# heehaw10.net
KiCad netlist of a schematic drawn in EAGLE
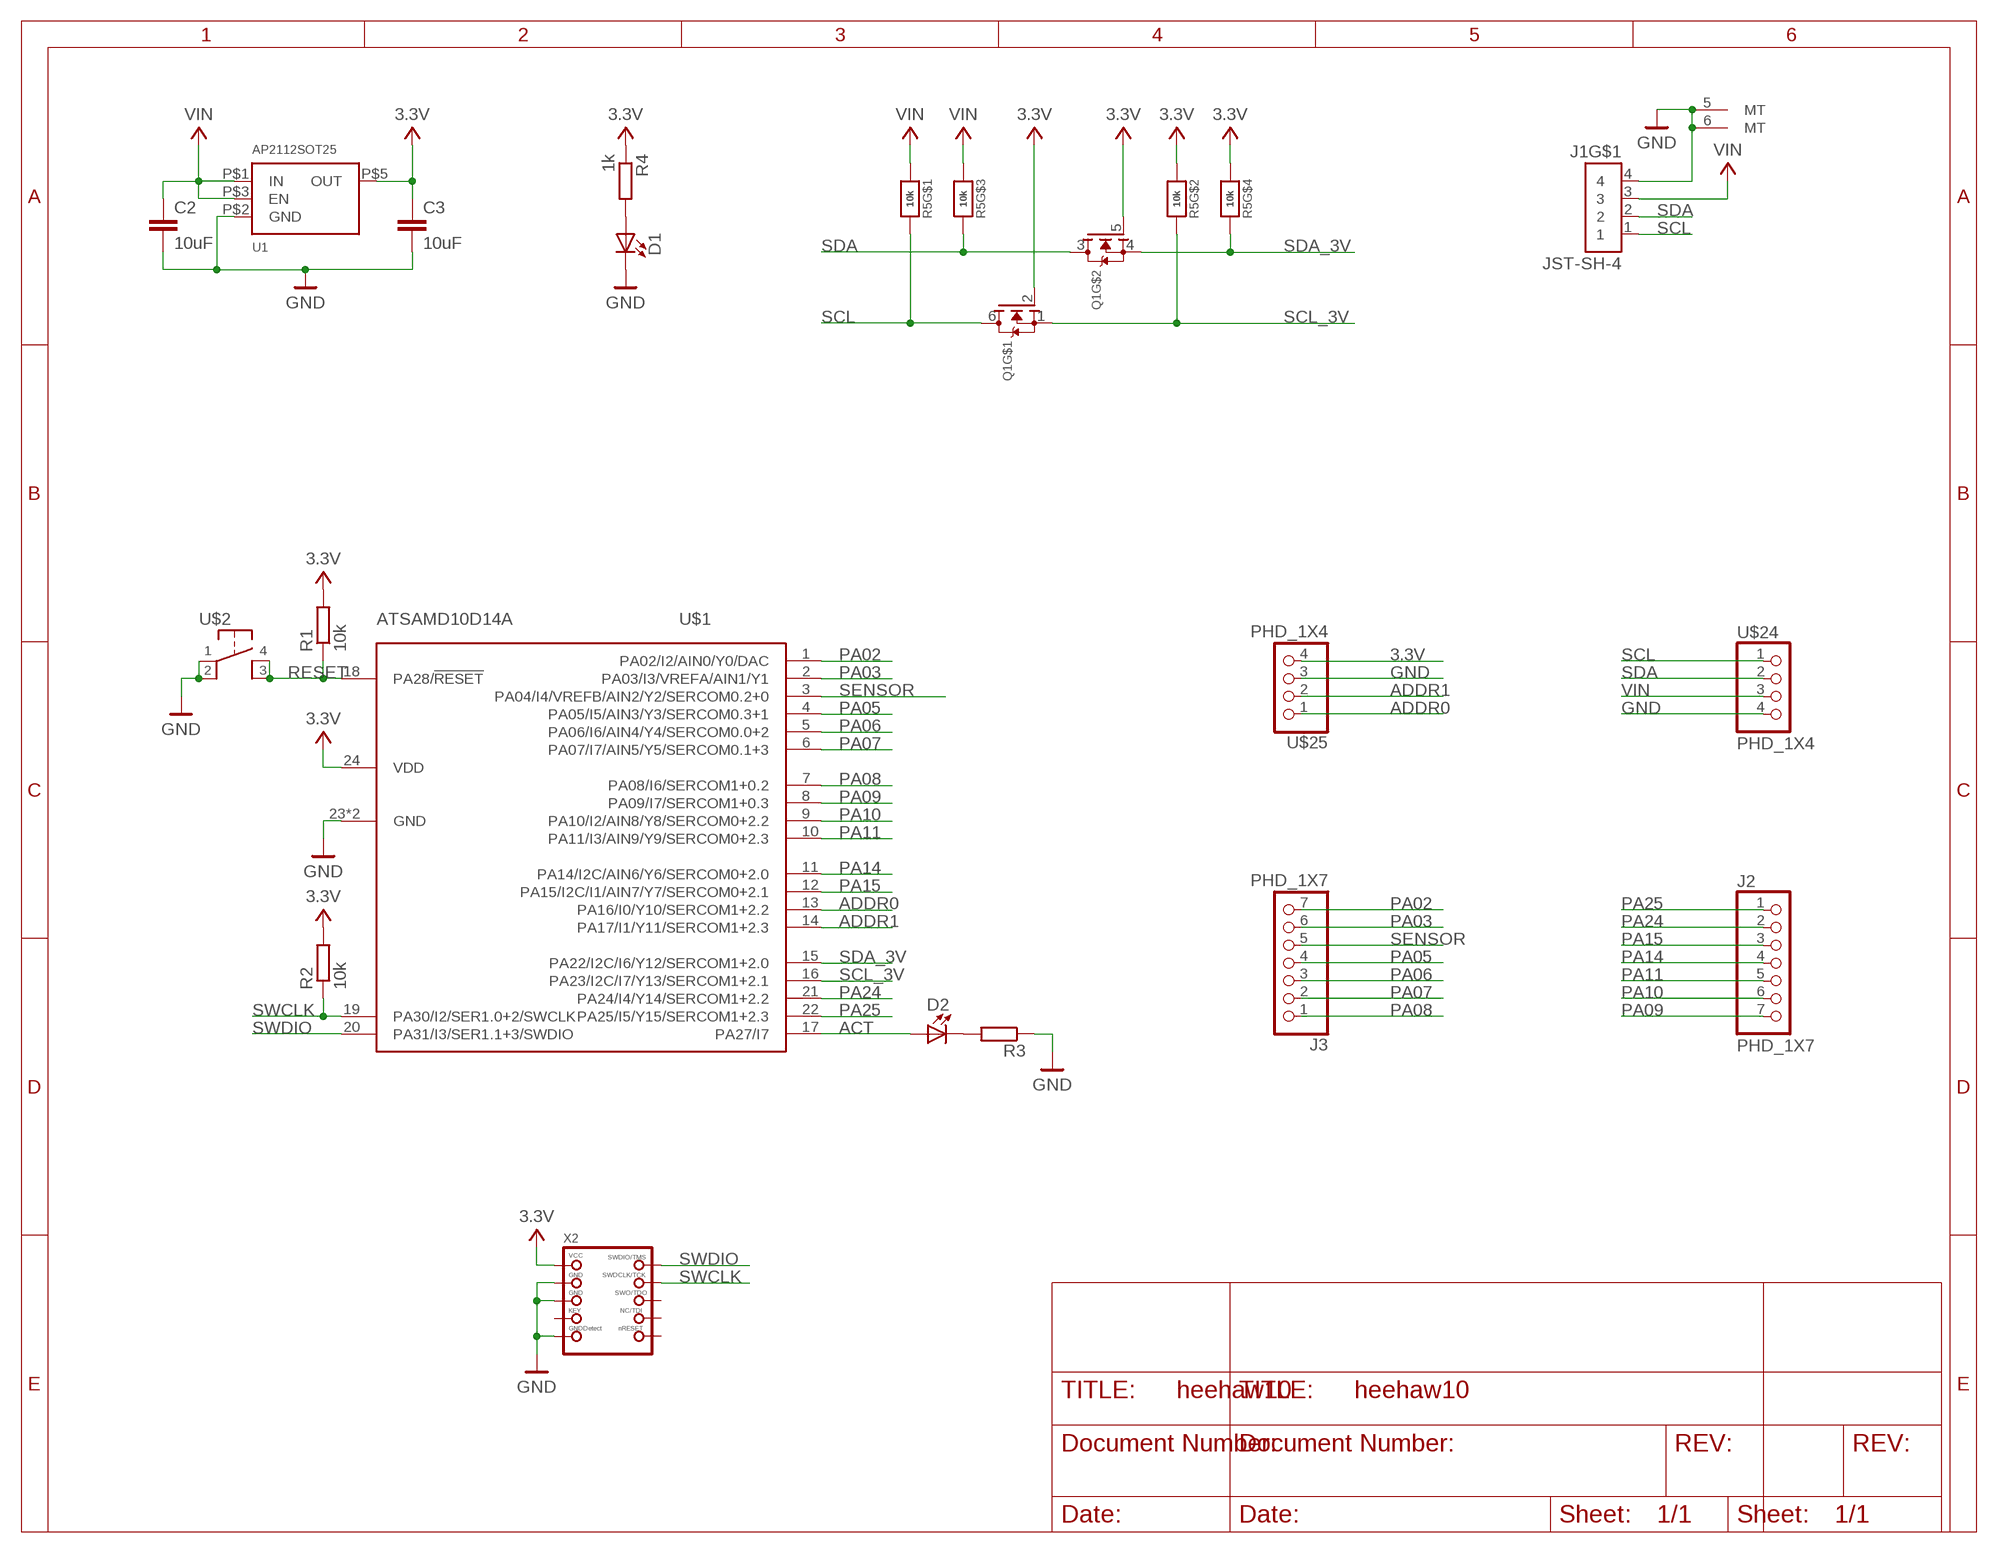
[diagram p0: schematic, sheet 1]

(export (version "E")
  (design (tool "Eeschema 10.0.6"))
  (components
    (comp (ref "C2")
      (value "10uF")
      (footprint "eagle-import:C0603")
      (libsource (lib "eagle-import") (part "C-EUC0603"))
    )
    (comp (ref "C3")
      (value "10uF")
      (footprint "eagle-import:C0603")
      (libsource (lib "eagle-import") (part "C-EUC0603"))
    )
    (comp (ref "D1")
      (value "SMD_LED0603")
      (footprint "eagle-import:LED0603")
      (libsource (lib "eagle-import") (part "SMD_LED0603"))
    )
    (comp (ref "D2")
      (value "SMD_LED0603")
      (footprint "eagle-import:LED0603")
      (libsource (lib "eagle-import") (part "SMD_LED0603"))
    )
    (comp (ref "J1")
      (value "JST-SH-4")
      (footprint "eagle-import:JST-S4B-SH-SM4-TB")
      (libsource (lib "eagle-import") (part "JST-SH-4"))
    )
    (comp (ref "J2")
      (value "PHD_1X7")
      (footprint "eagle-import:PHD_1X7")
      (libsource (lib "eagle-import") (part "PHD_1X7"))
    )
    (comp (ref "J3")
      (value "PHD_1X7")
      (footprint "eagle-import:PHD_1X7")
      (libsource (lib "eagle-import") (part "PHD_1X7"))
    )
    (comp (ref "Q1")
      (value "MOSFET-N_DUAL")
      (footprint "eagle-import:SOT363")
      (libsource (lib "eagle-import") (part "MOSFET-N_DUAL"))
    )
    (comp (ref "R1")
      (value "10k")
      (footprint "eagle-import:R0603")
      (libsource (lib "eagle-import") (part "R-EU_R0603"))
    )
    (comp (ref "R2")
      (value "10k")
      (footprint "eagle-import:R0603")
      (libsource (lib "eagle-import") (part "R-EU_R0603"))
    )
    (comp (ref "R3")
      (value "R-EU_R0603")
      (footprint "eagle-import:R0603")
      (libsource (lib "eagle-import") (part "R-EU_R0603"))
    )
    (comp (ref "R4")
      (value "1k")
      (footprint "eagle-import:R0603")
      (libsource (lib "eagle-import") (part "R-EU_R0603"))
    )
    (comp (ref "R5")
      (value "10k")
      (footprint "eagle-import:RESPACK_4X0603")
      (libsource (lib "eagle-import") (part "RESISTOR_4PACK"))
    )
    (comp (ref "U$1")
      (value "ATSAMD10D14A")
      (footprint "eagle-import:QFN24_4MM")
      (libsource (lib "eagle-import") (part "ATSAMD10D14A"))
    )
    (comp (ref "U$2")
      (value "PTS647")
      (footprint "eagle-import:PTS647")
      (libsource (lib "eagle-import") (part "PTS647"))
    )
    (comp (ref "U$24")
      (value "PHD_1X4")
      (footprint "eagle-import:PHD_1X4")
      (libsource (lib "eagle-import") (part "PHD_1X4"))
    )
    (comp (ref "U$25")
      (value "PHD_1X4")
      (footprint "eagle-import:PHD_1X4")
      (libsource (lib "eagle-import") (part "PHD_1X4"))
    )
    (comp (ref "U1")
      (value "AP2112SOT25")
      (footprint "eagle-import:SOT25")
      (libsource (lib "eagle-import") (part "AP2112SOT25"))
    )
    (comp (ref "X2")
      (value "SWD_2X5")
      (footprint "eagle-import:SWD_MINI")
      (libsource (lib "eagle-import") (part "SWD_2X5"))
    )
  )
  (nets
    (net (code "1") (name "/ACT") (class "Default")
      (node (ref "D2") (pin "2") (pinfunction "A_2") (pintype "passive"))
      (node (ref "U$1") (pin "17") (pinfunction "PA27/I7_17") (pintype "bidirectional"))
    )
    (net (code "2") (name "/ADDR0") (class "Default")
      (node (ref "U$1") (pin "13") (pinfunction "PA16/I0/Y10/SERCOM1+2.2_13") (pintype "bidirectional"))
      (node (ref "U$25") (pin "1") (pinfunction "1_1") (pintype "passive"))
    )
    (net (code "3") (name "/ADDR1") (class "Default")
      (node (ref "U$1") (pin "14") (pinfunction "PA17/I1/Y11/SERCOM1+2.3_14") (pintype "bidirectional"))
      (node (ref "U$25") (pin "2") (pinfunction "2_2") (pintype "passive"))
    )
    (net (code "4") (name "/PA02") (class "Default")
      (node (ref "J3") (pin "7") (pinfunction "7_7") (pintype "passive"))
      (node (ref "U$1") (pin "1") (pinfunction "PA02/I2/AIN0/Y0/DAC_1") (pintype "bidirectional"))
    )
    (net (code "5") (name "/PA03") (class "Default")
      (node (ref "J3") (pin "6") (pinfunction "6_6") (pintype "passive"))
      (node (ref "U$1") (pin "2") (pinfunction "PA03/I3/VREFA/AIN1/Y1_2") (pintype "bidirectional"))
    )
    (net (code "6") (name "/PA05") (class "Default")
      (node (ref "J3") (pin "4") (pinfunction "4_4") (pintype "passive"))
      (node (ref "U$1") (pin "4") (pinfunction "PA05/I5/AIN3/Y3/SERCOM0.3+1_4") (pintype "bidirectional"))
    )
    (net (code "7") (name "/PA06") (class "Default")
      (node (ref "J3") (pin "3") (pinfunction "3_3") (pintype "passive"))
      (node (ref "U$1") (pin "5") (pinfunction "PA06/I6/AIN4/Y4/SERCOM0.0+2_5") (pintype "bidirectional"))
    )
    (net (code "8") (name "/PA07") (class "Default")
      (node (ref "J3") (pin "2") (pinfunction "2_2") (pintype "passive"))
      (node (ref "U$1") (pin "6") (pinfunction "PA07/I7/AIN5/Y5/SERCOM0.1+3_6") (pintype "bidirectional"))
    )
    (net (code "9") (name "/PA08") (class "Default")
      (node (ref "J3") (pin "1") (pinfunction "1_1") (pintype "passive"))
      (node (ref "U$1") (pin "7") (pinfunction "PA08/I6/SERCOM1+0.2_7") (pintype "bidirectional"))
    )
    (net (code "10") (name "/PA09") (class "Default")
      (node (ref "J2") (pin "7") (pinfunction "7_7") (pintype "passive"))
      (node (ref "U$1") (pin "8") (pinfunction "PA09/I7/SERCOM1+0.3_8") (pintype "bidirectional"))
    )
    (net (code "11") (name "/PA10") (class "Default")
      (node (ref "J2") (pin "6") (pinfunction "6_6") (pintype "passive"))
      (node (ref "U$1") (pin "9") (pinfunction "PA10/I2/AIN8/Y8/SERCOM0+2.2_9") (pintype "bidirectional"))
    )
    (net (code "12") (name "/PA11") (class "Default")
      (node (ref "J2") (pin "5") (pinfunction "5_5") (pintype "passive"))
      (node (ref "U$1") (pin "10") (pinfunction "PA11/I3/AIN9/Y9/SERCOM0+2.3_10") (pintype "bidirectional"))
    )
    (net (code "13") (name "/PA14") (class "Default")
      (node (ref "J2") (pin "4") (pinfunction "4_4") (pintype "passive"))
      (node (ref "U$1") (pin "11") (pinfunction "PA14/I2C/AIN6/Y6/SERCOM0+2.0_11") (pintype "bidirectional"))
    )
    (net (code "14") (name "/PA15") (class "Default")
      (node (ref "J2") (pin "3") (pinfunction "3_3") (pintype "passive"))
      (node (ref "U$1") (pin "12") (pinfunction "PA15/I2C/I1/AIN7/Y7/SERCOM0+2.1_12") (pintype "bidirectional"))
    )
    (net (code "15") (name "/PA24") (class "Default")
      (node (ref "J2") (pin "2") (pinfunction "2_2") (pintype "passive"))
      (node (ref "U$1") (pin "21") (pinfunction "PA24/I4/Y14/SERCOM1+2.2_21") (pintype "bidirectional"))
    )
    (net (code "16") (name "/PA25") (class "Default")
      (node (ref "J2") (pin "1") (pinfunction "1_1") (pintype "passive"))
      (node (ref "U$1") (pin "22") (pinfunction "PA25/I5/Y15/SERCOM1+2.3_22") (pintype "bidirectional"))
    )
    (net (code "17") (name "/RESET") (class "Default")
      (node (ref "R1") (pin "1") (pinfunction "1_1") (pintype "passive"))
      (node (ref "U$1") (pin "18") (pinfunction "PA28/~{RESET}_18") (pintype "bidirectional"))
      (node (ref "U$2") (pin "3") (pinfunction "3_3") (pintype "bidirectional"))
      (node (ref "U$2") (pin "4") (pinfunction "4_4") (pintype "bidirectional"))
    )
    (net (code "18") (name "/SCL") (class "Default")
      (node (ref "J1") (pin "1") (pinfunction "1_1") (pintype "bidirectional"))
      (node (ref "Q1") (pin "6") (pinfunction "D_6") (pintype "bidirectional"))
      (node (ref "R5") (pin "8") (pinfunction "2_8") (pintype "passive"))
      (node (ref "U$24") (pin "1") (pinfunction "1_1") (pintype "passive"))
    )
    (net (code "19") (name "/SCL_3V") (class "Default")
      (node (ref "Q1") (pin "1") (pinfunction "S_1") (pintype "bidirectional"))
      (node (ref "R5") (pin "7") (pinfunction "2_7") (pintype "passive"))
      (node (ref "U$1") (pin "16") (pinfunction "PA23/I2C/I7/Y13/SERCOM1+2.1_16") (pintype "bidirectional"))
    )
    (net (code "20") (name "/SDA") (class "Default")
      (node (ref "J1") (pin "2") (pinfunction "2_2") (pintype "bidirectional"))
      (node (ref "Q1") (pin "3") (pinfunction "D_3") (pintype "bidirectional"))
      (node (ref "R5") (pin "6") (pinfunction "2_6") (pintype "passive"))
      (node (ref "U$24") (pin "2") (pinfunction "2_2") (pintype "passive"))
    )
    (net (code "21") (name "/SDA_3V") (class "Default")
      (node (ref "Q1") (pin "4") (pinfunction "S_4") (pintype "bidirectional"))
      (node (ref "R5") (pin "5") (pinfunction "2_5") (pintype "passive"))
      (node (ref "U$1") (pin "15") (pinfunction "PA22/I2C/I6/Y12/SERCOM1+2.0_15") (pintype "bidirectional"))
    )
    (net (code "22") (name "/SENSOR") (class "Default")
      (node (ref "J3") (pin "5") (pinfunction "5_5") (pintype "passive"))
      (node (ref "U$1") (pin "3") (pinfunction "PA04/I4/VREFB/AIN2/Y2/SERCOM0.2+0_3") (pintype "bidirectional"))
    )
    (net (code "23") (name "/SWCLK") (class "Default")
      (node (ref "R2") (pin "1") (pinfunction "1_1") (pintype "passive"))
      (node (ref "U$1") (pin "19") (pinfunction "PA30/I2/SER1.0+2/SWCLK_19") (pintype "bidirectional"))
      (node (ref "X2") (pin "4") (pinfunction "SWDCLK_4") (pintype "bidirectional"))
    )
    (net (code "24") (name "/SWDIO") (class "Default")
      (node (ref "U$1") (pin "20") (pinfunction "PA31/I3/SER1.1+3/SWDIO_20") (pintype "bidirectional"))
      (node (ref "X2") (pin "2") (pinfunction "SWDIO_2") (pintype "bidirectional"))
    )
    (net (code "25") (name "3.3V") (class "Default")
      (node (ref "C3") (pin "1") (pinfunction "1_1") (pintype "passive"))
      (node (ref "Q1") (pin "2") (pinfunction "G_2") (pintype "bidirectional"))
      (node (ref "Q1") (pin "5") (pinfunction "G_5") (pintype "bidirectional"))
      (node (ref "R1") (pin "2") (pinfunction "2_2") (pintype "passive"))
      (node (ref "R2") (pin "2") (pinfunction "2_2") (pintype "passive"))
      (node (ref "R4") (pin "1") (pinfunction "1_1") (pintype "passive"))
      (node (ref "R5") (pin "2") (pinfunction "1_2") (pintype "passive"))
      (node (ref "R5") (pin "4") (pinfunction "1_4") (pintype "passive"))
      (node (ref "U$1") (pin "24") (pinfunction "VDD_24") (pintype "power_in"))
      (node (ref "U$25") (pin "4") (pinfunction "4_4") (pintype "passive"))
      (node (ref "U1") (pin "P$5") (pinfunction "OUT_P$5") (pintype "power_in"))
      (node (ref "X2") (pin "1") (pinfunction "VCC_1") (pintype "power_in"))
    )
    (net (code "26") (name "GND") (class "Default")
      (node (ref "C2") (pin "2") (pinfunction "2_2") (pintype "passive"))
      (node (ref "C3") (pin "2") (pinfunction "2_2") (pintype "passive"))
      (node (ref "D1") (pin "1") (pinfunction "C_1") (pintype "passive"))
      (node (ref "J1") (pin "4") (pinfunction "4_4") (pintype "bidirectional"))
      (node (ref "J1") (pin "5") (pinfunction "MT_5") (pintype "bidirectional"))
      (node (ref "J1") (pin "6") (pinfunction "MT_6") (pintype "bidirectional"))
      (node (ref "R3") (pin "1") (pinfunction "1_1") (pintype "passive"))
      (node (ref "U$1") (pin "23") (pinfunction "GND_23") (pintype "power_in"))
      (node (ref "U$1") (pin "THERM") (pinfunction "GND_THERM") (pintype "power_in"))
      (node (ref "U$2") (pin "1") (pinfunction "1_1") (pintype "bidirectional"))
      (node (ref "U$2") (pin "2") (pinfunction "2_2") (pintype "bidirectional"))
      (node (ref "U$24") (pin "4") (pinfunction "4_4") (pintype "passive"))
      (node (ref "U$25") (pin "3") (pinfunction "3_3") (pintype "passive"))
      (node (ref "U1") (pin "P$2") (pinfunction "GND_P$2") (pintype "power_in"))
      (node (ref "X2") (pin "3") (pinfunction "GND_3") (pintype "power_in"))
      (node (ref "X2") (pin "5") (pinfunction "GND_5") (pintype "power_in"))
      (node (ref "X2") (pin "9") (pinfunction "GNDDETECT_9") (pintype "bidirectional"))
    )
    (net (code "27") (name "Net-(D1-A)") (class "Default")
      (node (ref "D1") (pin "2") (pinfunction "A_2") (pintype "passive"))
      (node (ref "R4") (pin "2") (pinfunction "2_2") (pintype "passive"))
    )
    (net (code "28") (name "Net-(D2-C)") (class "Default")
      (node (ref "D2") (pin "1") (pinfunction "C_1") (pintype "passive"))
      (node (ref "R3") (pin "2") (pinfunction "2_2") (pintype "passive"))
    )
    (net (code "29") (name "VIN") (class "Default")
      (node (ref "C2") (pin "1") (pinfunction "1_1") (pintype "passive"))
      (node (ref "J1") (pin "3") (pinfunction "3_3") (pintype "bidirectional"))
      (node (ref "R5") (pin "1") (pinfunction "1_1") (pintype "passive"))
      (node (ref "R5") (pin "3") (pinfunction "1_3") (pintype "passive"))
      (node (ref "U$24") (pin "3") (pinfunction "3_3") (pintype "passive"))
      (node (ref "U1") (pin "P$1") (pinfunction "IN_P$1") (pintype "power_in"))
      (node (ref "U1") (pin "P$3") (pinfunction "EN_P$3") (pintype "input"))
    )
    (net (code "30") (name "unconnected-(X2-KEY-Pad7)") (class "Default")
      (node (ref "X2") (pin "7") (pinfunction "KEY_7") (pintype "bidirectional"))
    )
    (net (code "31") (name "unconnected-(X2-NRESET-Pad10)") (class "Default")
      (node (ref "X2") (pin "10") (pinfunction "NRESET_10") (pintype "bidirectional"))
    )
    (net (code "32") (name "unconnected-(X2-SWO-Pad6)") (class "Default")
      (node (ref "X2") (pin "6") (pinfunction "SWO_6") (pintype "bidirectional"))
    )
    (net (code "33") (name "unconnected-(X2-TDI-Pad8)") (class "Default")
      (node (ref "X2") (pin "8") (pinfunction "TDI_8") (pintype "bidirectional"))
    )
  )
)
